# airlight.net
KiCad netlist of a schematic drawn in EAGLE
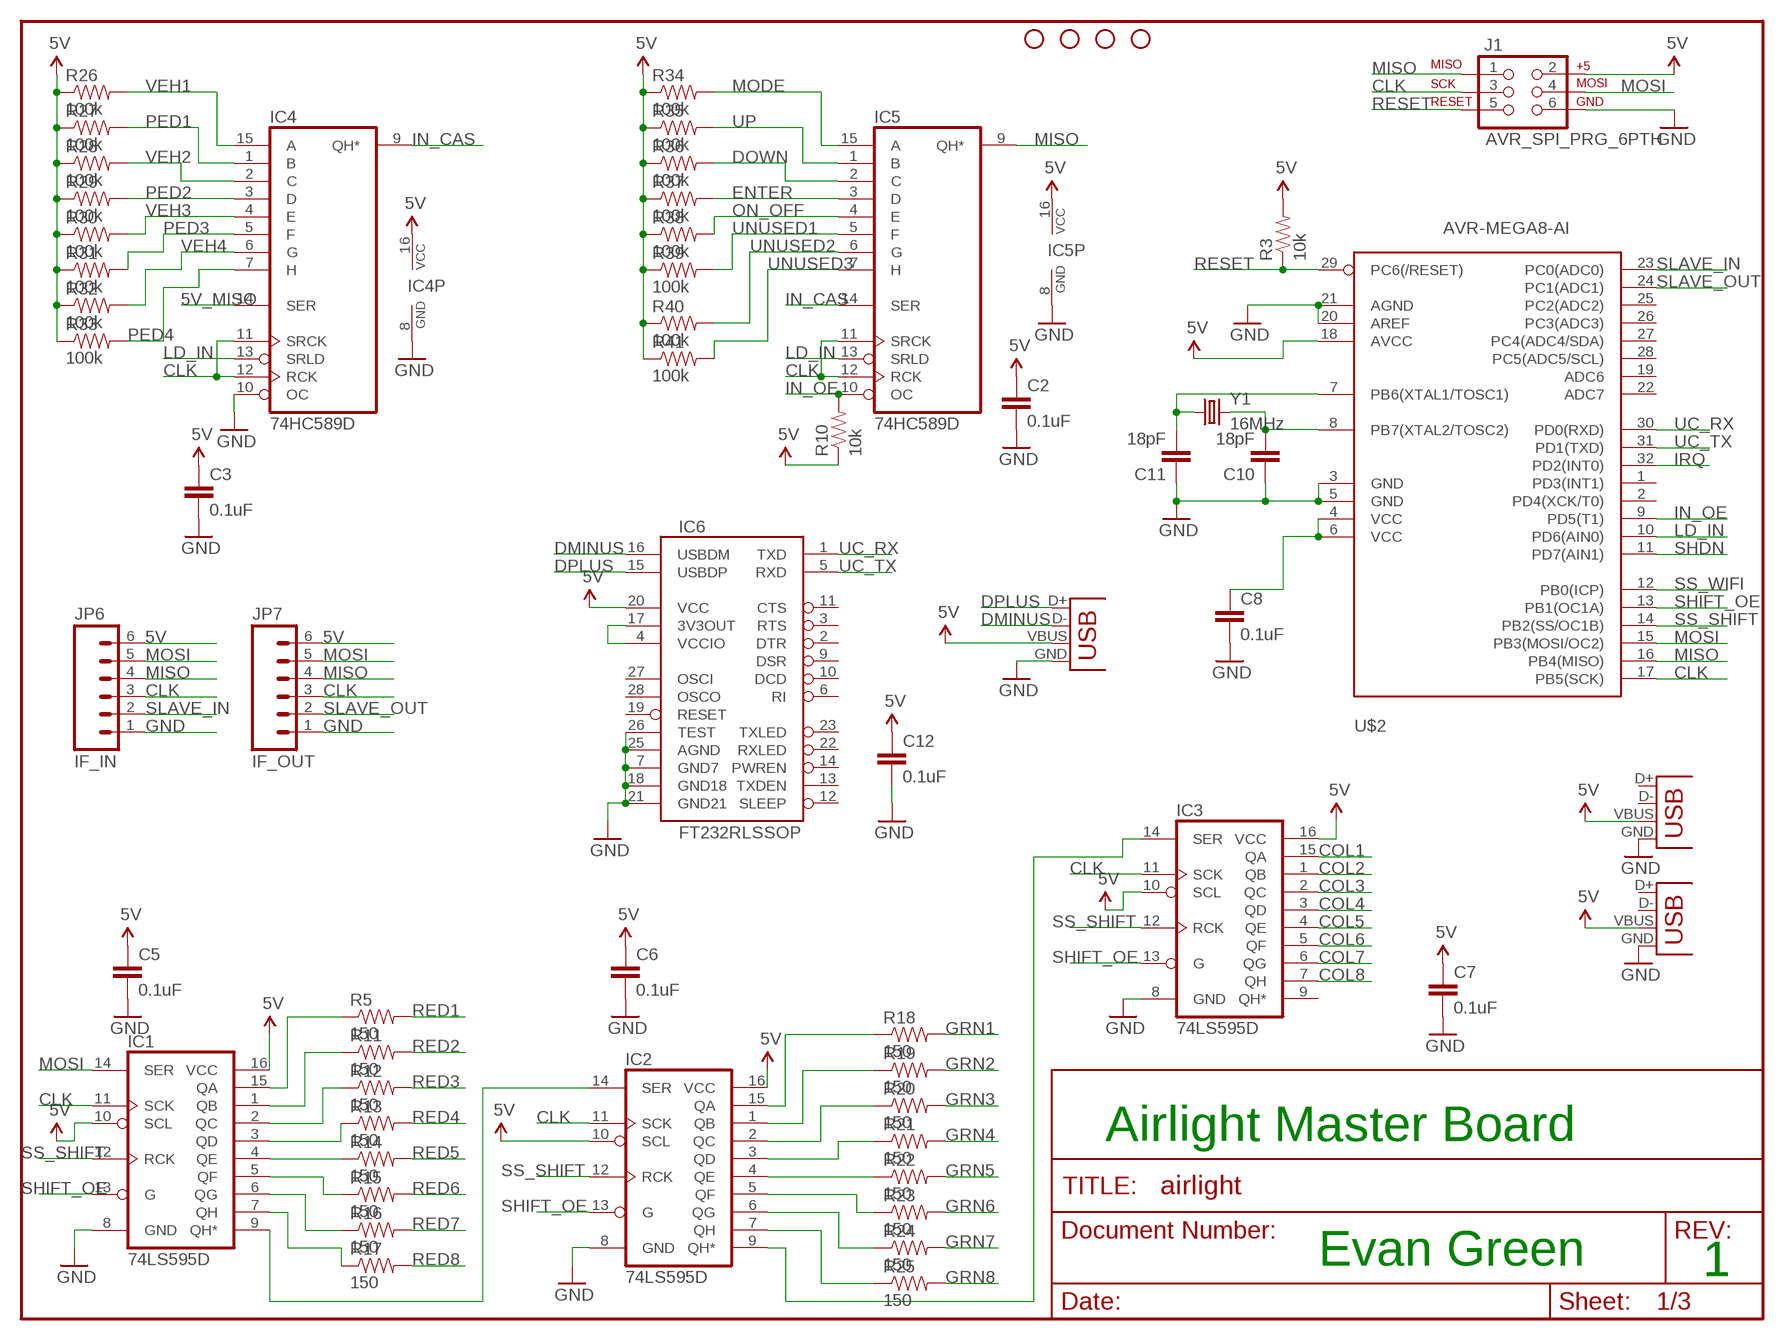
[diagram p0: schematic, sheet 1]
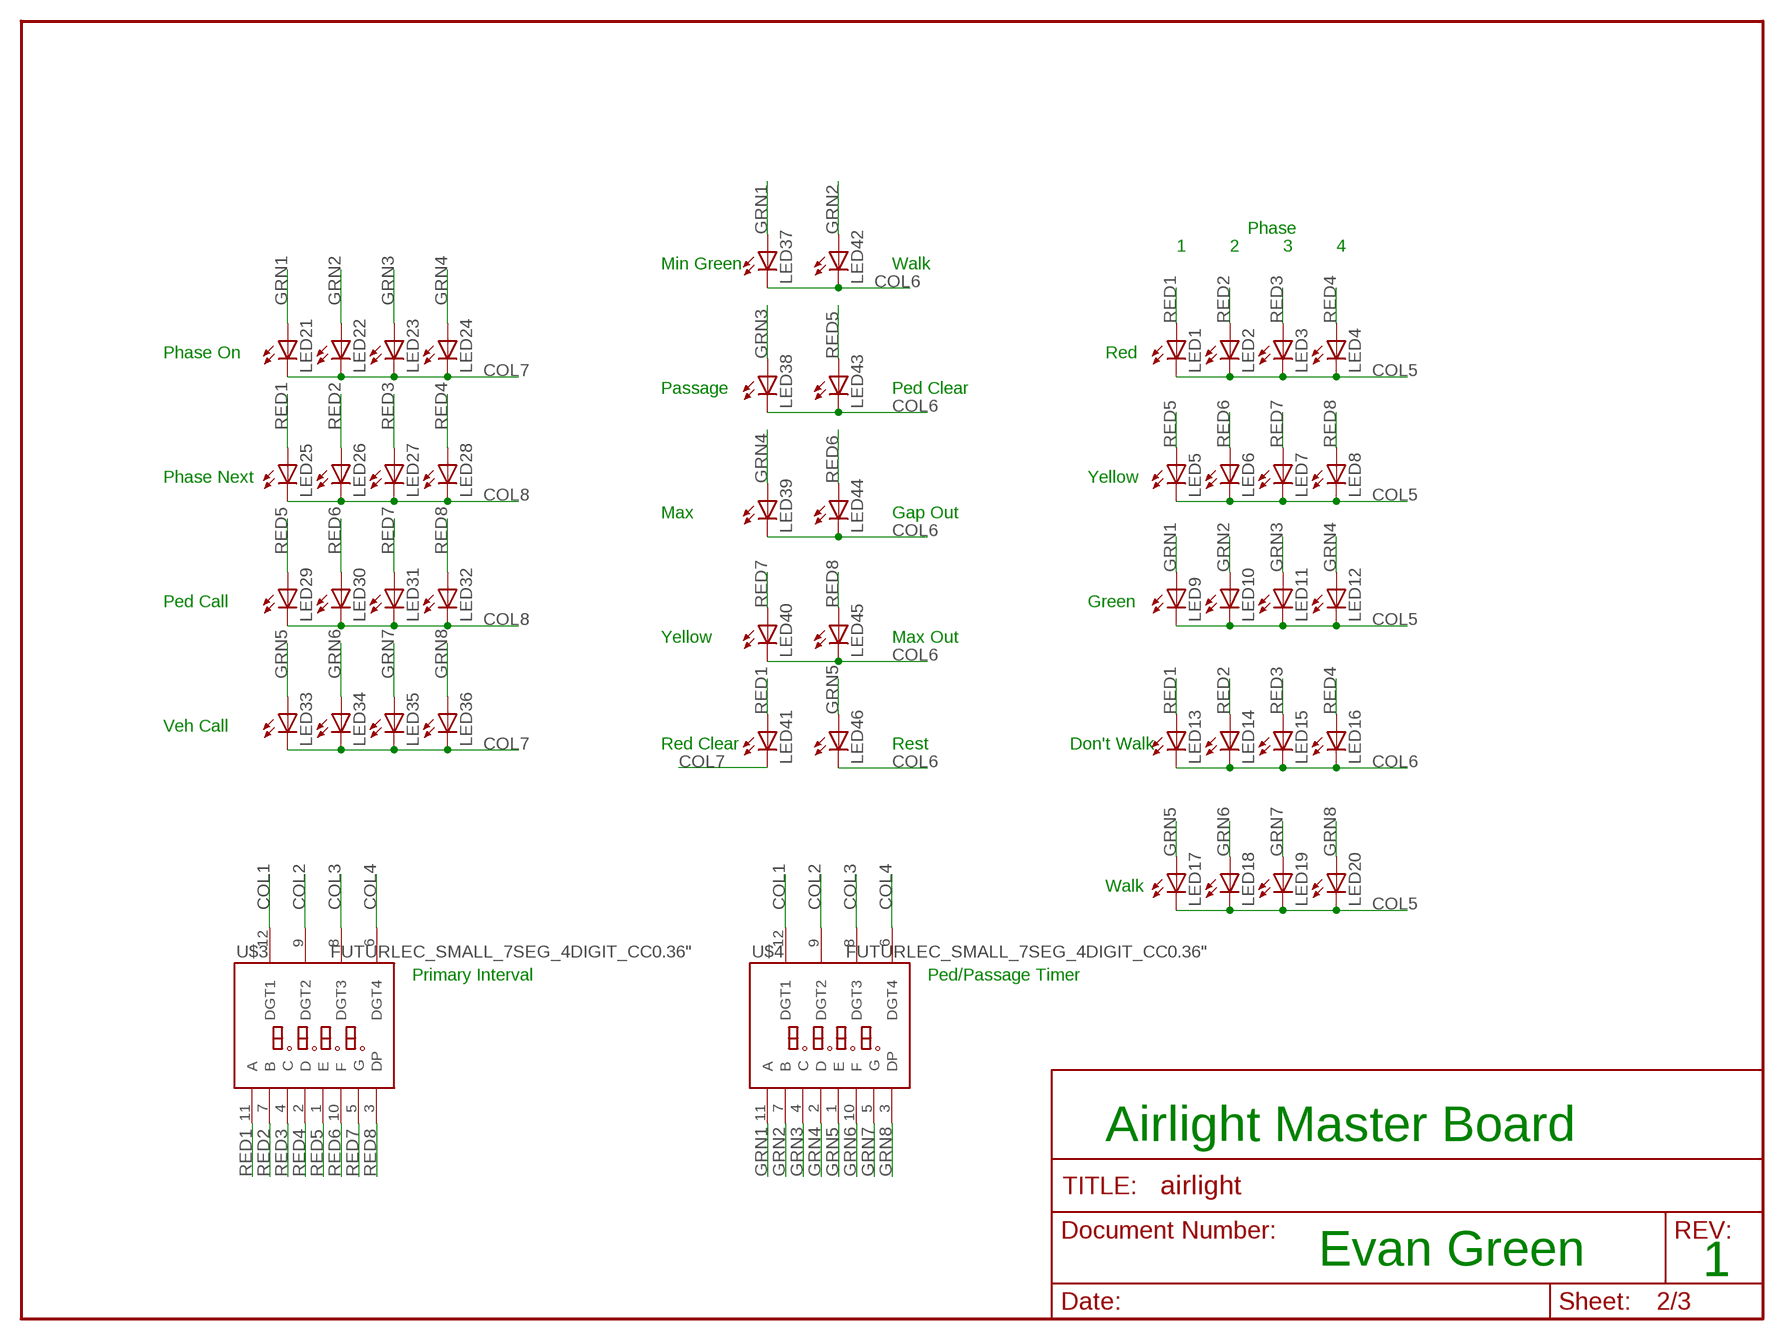
[diagram p1: schematic, sheet 2]
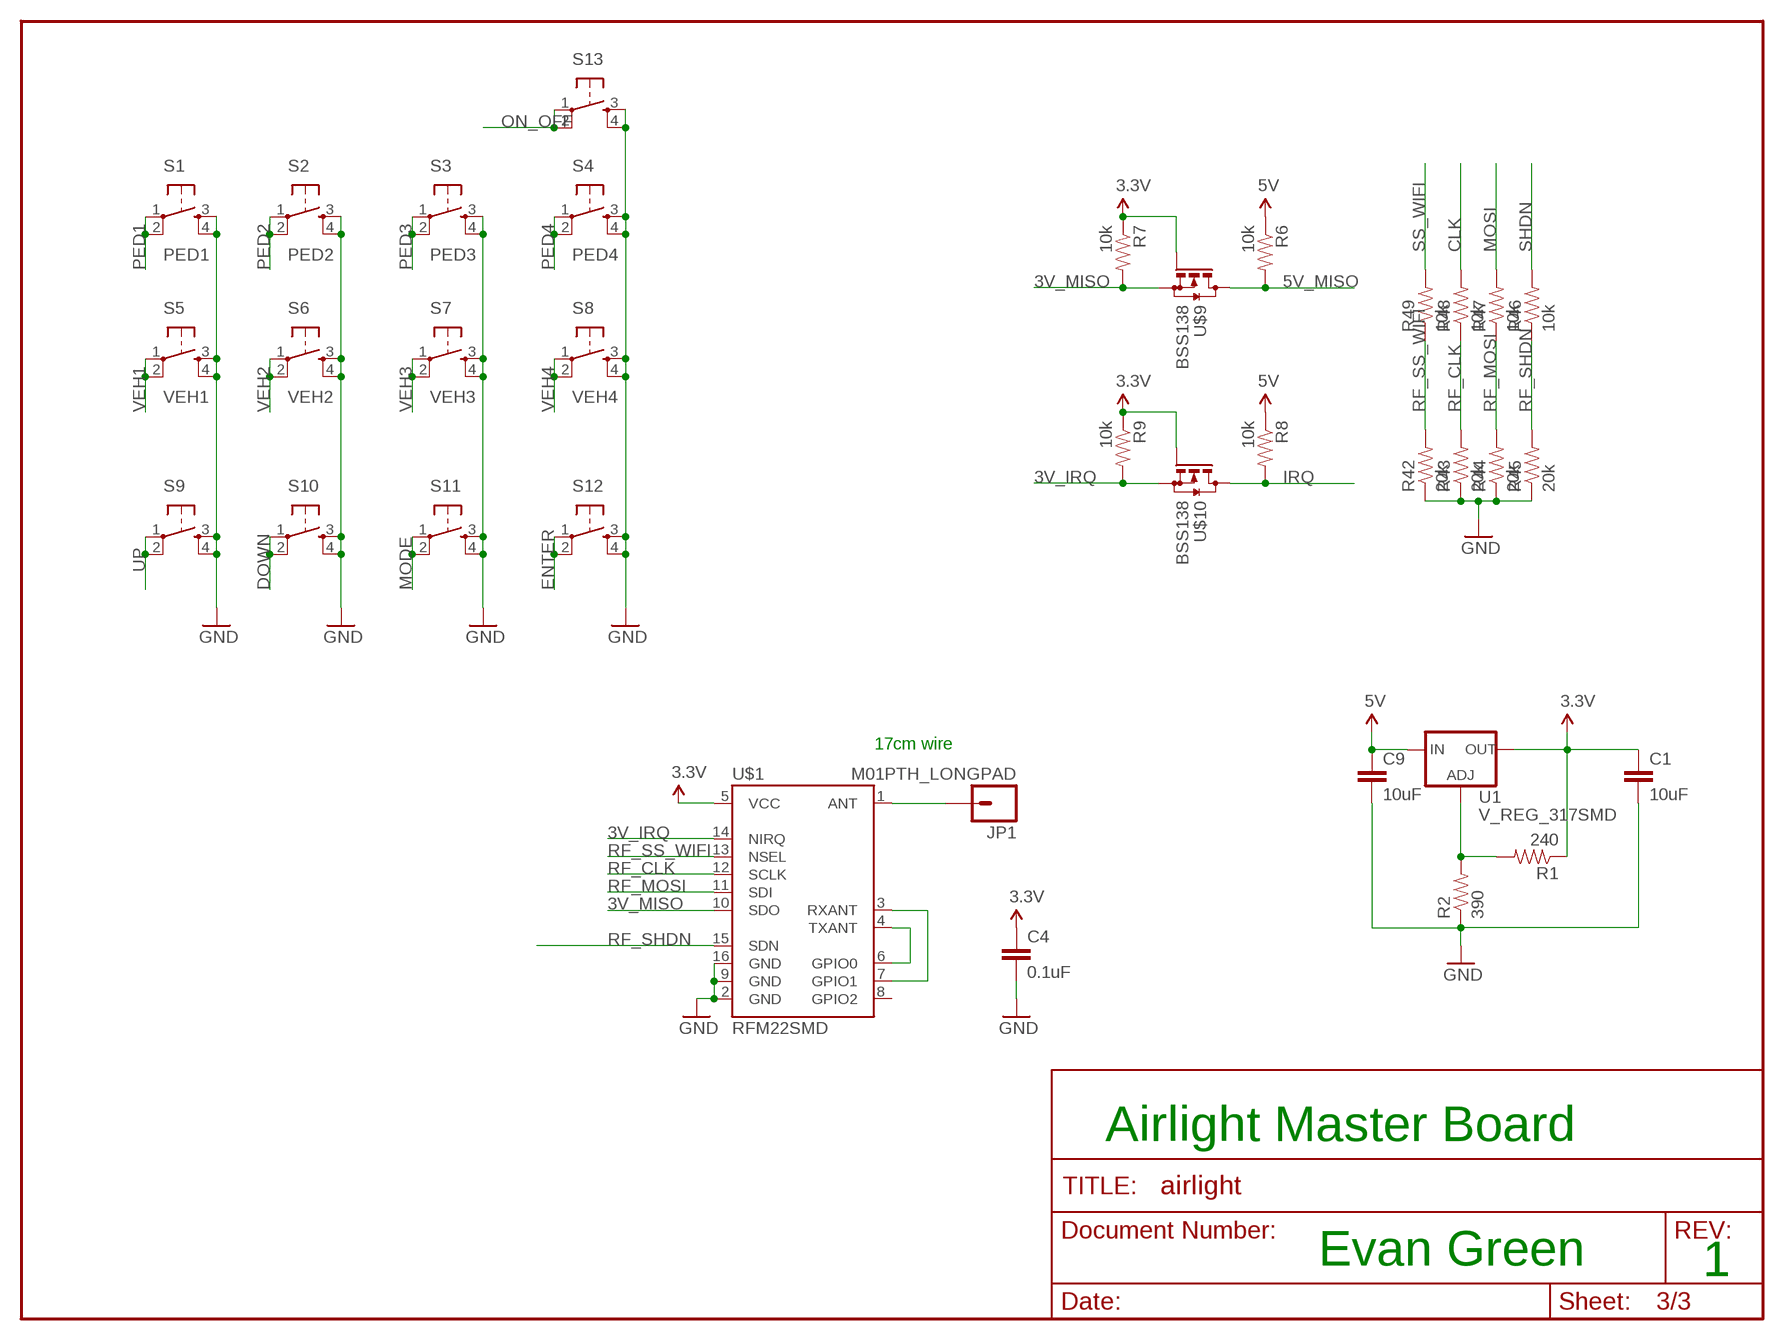
[diagram p2: schematic, sheet 3]

(export (version "E")
  (design (tool "Eeschema 10.0.6"))
  (components
    (comp (ref "LED1")
      (value "LED5MM")
      (footprint "eagle-import:LED5MM")
      (libsource (lib "eagle-import") (part "LED5MM"))
    )
    (comp (ref "LED2")
      (value "LED5MM")
      (footprint "eagle-import:LED5MM")
      (libsource (lib "eagle-import") (part "LED5MM"))
    )
    (comp (ref "LED3")
      (value "LED5MM")
      (footprint "eagle-import:LED5MM")
      (libsource (lib "eagle-import") (part "LED5MM"))
    )
    (comp (ref "LED4")
      (value "LED5MM")
      (footprint "eagle-import:LED5MM")
      (libsource (lib "eagle-import") (part "LED5MM"))
    )
    (comp (ref "LED5")
      (value "LED5MM")
      (footprint "eagle-import:LED5MM")
      (libsource (lib "eagle-import") (part "LED5MM"))
    )
    (comp (ref "LED6")
      (value "LED5MM")
      (footprint "eagle-import:LED5MM")
      (libsource (lib "eagle-import") (part "LED5MM"))
    )
    (comp (ref "LED7")
      (value "LED5MM")
      (footprint "eagle-import:LED5MM")
      (libsource (lib "eagle-import") (part "LED5MM"))
    )
    (comp (ref "LED8")
      (value "LED5MM")
      (footprint "eagle-import:LED5MM")
      (libsource (lib "eagle-import") (part "LED5MM"))
    )
    (comp (ref "LED9")
      (value "LED5MM")
      (footprint "eagle-import:LED5MM")
      (libsource (lib "eagle-import") (part "LED5MM"))
    )
    (comp (ref "LED10")
      (value "LED5MM")
      (footprint "eagle-import:LED5MM")
      (libsource (lib "eagle-import") (part "LED5MM"))
    )
    (comp (ref "LED11")
      (value "LED5MM")
      (footprint "eagle-import:LED5MM")
      (libsource (lib "eagle-import") (part "LED5MM"))
    )
    (comp (ref "LED12")
      (value "LED5MM")
      (footprint "eagle-import:LED5MM")
      (libsource (lib "eagle-import") (part "LED5MM"))
    )
    (comp (ref "LED13")
      (value "LED5MM")
      (footprint "eagle-import:LED5MM")
      (libsource (lib "eagle-import") (part "LED5MM"))
    )
    (comp (ref "LED14")
      (value "LED5MM")
      (footprint "eagle-import:LED5MM")
      (libsource (lib "eagle-import") (part "LED5MM"))
    )
    (comp (ref "LED15")
      (value "LED5MM")
      (footprint "eagle-import:LED5MM")
      (libsource (lib "eagle-import") (part "LED5MM"))
    )
    (comp (ref "LED16")
      (value "LED5MM")
      (footprint "eagle-import:LED5MM")
      (libsource (lib "eagle-import") (part "LED5MM"))
    )
    (comp (ref "LED17")
      (value "LED5MM")
      (footprint "eagle-import:LED5MM")
      (libsource (lib "eagle-import") (part "LED5MM"))
    )
    (comp (ref "LED18")
      (value "LED5MM")
      (footprint "eagle-import:LED5MM")
      (libsource (lib "eagle-import") (part "LED5MM"))
    )
    (comp (ref "LED19")
      (value "LED5MM")
      (footprint "eagle-import:LED5MM")
      (libsource (lib "eagle-import") (part "LED5MM"))
    )
    (comp (ref "LED20")
      (value "LED5MM")
      (footprint "eagle-import:LED5MM")
      (libsource (lib "eagle-import") (part "LED5MM"))
    )
    (comp (ref "LED21")
      (value "LED5MM")
      (footprint "eagle-import:LED5MM")
      (libsource (lib "eagle-import") (part "LED5MM"))
    )
    (comp (ref "LED22")
      (value "LED5MM")
      (footprint "eagle-import:LED5MM")
      (libsource (lib "eagle-import") (part "LED5MM"))
    )
    (comp (ref "LED23")
      (value "LED5MM")
      (footprint "eagle-import:LED5MM")
      (libsource (lib "eagle-import") (part "LED5MM"))
    )
    (comp (ref "LED24")
      (value "LED5MM")
      (footprint "eagle-import:LED5MM")
      (libsource (lib "eagle-import") (part "LED5MM"))
    )
    (comp (ref "LED25")
      (value "LED5MM")
      (footprint "eagle-import:LED5MM")
      (libsource (lib "eagle-import") (part "LED5MM"))
    )
    (comp (ref "LED26")
      (value "LED5MM")
      (footprint "eagle-import:LED5MM")
      (libsource (lib "eagle-import") (part "LED5MM"))
    )
    (comp (ref "LED27")
      (value "LED5MM")
      (footprint "eagle-import:LED5MM")
      (libsource (lib "eagle-import") (part "LED5MM"))
    )
    (comp (ref "LED28")
      (value "LED5MM")
      (footprint "eagle-import:LED5MM")
      (libsource (lib "eagle-import") (part "LED5MM"))
    )
    (comp (ref "LED29")
      (value "LED5MM")
      (footprint "eagle-import:LED5MM")
      (libsource (lib "eagle-import") (part "LED5MM"))
    )
    (comp (ref "LED30")
      (value "LED5MM")
      (footprint "eagle-import:LED5MM")
      (libsource (lib "eagle-import") (part "LED5MM"))
    )
    (comp (ref "LED31")
      (value "LED5MM")
      (footprint "eagle-import:LED5MM")
      (libsource (lib "eagle-import") (part "LED5MM"))
    )
    (comp (ref "LED32")
      (value "LED5MM")
      (footprint "eagle-import:LED5MM")
      (libsource (lib "eagle-import") (part "LED5MM"))
    )
    (comp (ref "LED33")
      (value "LED5MM")
      (footprint "eagle-import:LED5MM")
      (libsource (lib "eagle-import") (part "LED5MM"))
    )
    (comp (ref "LED34")
      (value "LED5MM")
      (footprint "eagle-import:LED5MM")
      (libsource (lib "eagle-import") (part "LED5MM"))
    )
    (comp (ref "LED35")
      (value "LED5MM")
      (footprint "eagle-import:LED5MM")
      (libsource (lib "eagle-import") (part "LED5MM"))
    )
    (comp (ref "LED36")
      (value "LED5MM")
      (footprint "eagle-import:LED5MM")
      (libsource (lib "eagle-import") (part "LED5MM"))
    )
    (comp (ref "LED37")
      (value "LED5MM")
      (footprint "eagle-import:LED5MM")
      (libsource (lib "eagle-import") (part "LED5MM"))
    )
    (comp (ref "LED38")
      (value "LED5MM")
      (footprint "eagle-import:LED5MM")
      (libsource (lib "eagle-import") (part "LED5MM"))
    )
    (comp (ref "LED39")
      (value "LED5MM")
      (footprint "eagle-import:LED5MM")
      (libsource (lib "eagle-import") (part "LED5MM"))
    )
    (comp (ref "LED40")
      (value "LED5MM")
      (footprint "eagle-import:LED5MM")
      (libsource (lib "eagle-import") (part "LED5MM"))
    )
    (comp (ref "LED41")
      (value "LED5MM")
      (footprint "eagle-import:LED5MM")
      (libsource (lib "eagle-import") (part "LED5MM"))
    )
    (comp (ref "LED42")
      (value "LED5MM")
      (footprint "eagle-import:LED5MM")
      (libsource (lib "eagle-import") (part "LED5MM"))
    )
    (comp (ref "LED43")
      (value "LED5MM")
      (footprint "eagle-import:LED5MM")
      (libsource (lib "eagle-import") (part "LED5MM"))
    )
    (comp (ref "LED44")
      (value "LED5MM")
      (footprint "eagle-import:LED5MM")
      (libsource (lib "eagle-import") (part "LED5MM"))
    )
    (comp (ref "LED45")
      (value "LED5MM")
      (footprint "eagle-import:LED5MM")
      (libsource (lib "eagle-import") (part "LED5MM"))
    )
    (comp (ref "LED46")
      (value "LED5MM")
      (footprint "eagle-import:LED5MM")
      (libsource (lib "eagle-import") (part "LED5MM"))
    )
    (comp (ref "U$3")
      (value "FUTURLEC_SMALL_7SEG_4DIGIT_CC0.36\"")
      (footprint "eagle-import:FUTURLEC_SMALL_7SEG_4DIGIT_CC")
      (libsource (lib "eagle-import") (part "FUTURLEC_SMALL_7SEG_4DIGIT_CC0.36{dblquote}"))
    )
    (comp (ref "U$4")
      (value "FUTURLEC_SMALL_7SEG_4DIGIT_CC0.36\"")
      (footprint "eagle-import:FUTURLEC_SMALL_7SEG_4DIGIT_CC")
      (libsource (lib "eagle-import") (part "FUTURLEC_SMALL_7SEG_4DIGIT_CC0.36{dblquote}"))
    )
    (comp (ref "C2")
      (value "0.1uF")
      (footprint "eagle-import:0402-CAP")
      (libsource (lib "eagle-import") (part "CAP0402-CAP"))
    )
    (comp (ref "C3")
      (value "0.1uF")
      (footprint "eagle-import:0402-CAP")
      (libsource (lib "eagle-import") (part "CAP0402-CAP"))
    )
    (comp (ref "C5")
      (value "0.1uF")
      (footprint "eagle-import:0402-CAP")
      (libsource (lib "eagle-import") (part "CAP0402-CAP"))
    )
    (comp (ref "C6")
      (value "0.1uF")
      (footprint "eagle-import:0402-CAP")
      (libsource (lib "eagle-import") (part "CAP0402-CAP"))
    )
    (comp (ref "C7")
      (value "0.1uF")
      (footprint "eagle-import:0402-CAP")
      (libsource (lib "eagle-import") (part "CAP0402-CAP"))
    )
    (comp (ref "C8")
      (value "0.1uF")
      (footprint "eagle-import:0402-CAP")
      (libsource (lib "eagle-import") (part "CAP0402-CAP"))
    )
    (comp (ref "C10")
      (value "18pF")
      (footprint "eagle-import:0402-CAP")
      (libsource (lib "eagle-import") (part "CAP0402-CAP"))
    )
    (comp (ref "C11")
      (value "18pF")
      (footprint "eagle-import:0402-CAP")
      (libsource (lib "eagle-import") (part "CAP0402-CAP"))
    )
    (comp (ref "C12")
      (value "0.1uF")
      (footprint "eagle-import:0402-CAP")
      (libsource (lib "eagle-import") (part "CAP0402-CAP"))
    )
    (comp (ref "IC1")
      (value "74LS595D")
      (footprint "eagle-import:SO16")
      (libsource (lib "eagle-import") (part "74595DLS"))
    )
    (comp (ref "IC2")
      (value "74LS595D")
      (footprint "eagle-import:SO16")
      (libsource (lib "eagle-import") (part "74595DLS"))
    )
    (comp (ref "IC3")
      (value "74LS595D")
      (footprint "eagle-import:SO16")
      (libsource (lib "eagle-import") (part "74595DLS"))
    )
    (comp (ref "IC4")
      (value "74HC589D")
      (footprint "eagle-import:SO16")
      (libsource (lib "eagle-import") (part "74589DHC"))
    )
    (comp (ref "IC5")
      (value "74HC589D")
      (footprint "eagle-import:SO16")
      (libsource (lib "eagle-import") (part "74589DHC"))
    )
    (comp (ref "IC6")
      (value "FT232RLSSOP")
      (footprint "eagle-import:SSOP28DB")
      (libsource (lib "eagle-import") (part "FT232RLSSOP"))
    )
    (comp (ref "J1")
      (value "AVR_SPI_PRG_6PTH")
      (footprint "eagle-import:2X3")
      (libsource (lib "eagle-import") (part "AVR_SPI_PRG_6PTH"))
    )
    (comp (ref "JP2")
      (value "STAND-OFF")
      (footprint "eagle-import:STAND-OFF")
      (libsource (lib "eagle-import") (part "STAND-OFF"))
    )
    (comp (ref "JP3")
      (value "STAND-OFF")
      (footprint "eagle-import:STAND-OFF")
      (libsource (lib "eagle-import") (part "STAND-OFF"))
    )
    (comp (ref "JP4")
      (value "STAND-OFF")
      (footprint "eagle-import:STAND-OFF")
      (libsource (lib "eagle-import") (part "STAND-OFF"))
    )
    (comp (ref "JP5")
      (value "STAND-OFF")
      (footprint "eagle-import:STAND-OFF")
      (libsource (lib "eagle-import") (part "STAND-OFF"))
    )
    (comp (ref "JP6")
      (value "IF_IN")
      (footprint "eagle-import:1X06")
      (libsource (lib "eagle-import") (part "M06SIP"))
    )
    (comp (ref "JP7")
      (value "IF_OUT")
      (footprint "eagle-import:1X06")
      (libsource (lib "eagle-import") (part "M06SIP"))
    )
    (comp (ref "R3")
      (value "10k")
      (footprint "eagle-import:0402-RES")
      (libsource (lib "eagle-import") (part "RESISTOR0402-RES"))
    )
    (comp (ref "R5")
      (value "150")
      (footprint "eagle-import:0402-RES")
      (libsource (lib "eagle-import") (part "RESISTOR0402-RES"))
    )
    (comp (ref "R10")
      (value "10k")
      (footprint "eagle-import:0402-RES")
      (libsource (lib "eagle-import") (part "RESISTOR0402-RES"))
    )
    (comp (ref "R11")
      (value "150")
      (footprint "eagle-import:0402-RES")
      (libsource (lib "eagle-import") (part "RESISTOR0402-RES"))
    )
    (comp (ref "R12")
      (value "150")
      (footprint "eagle-import:0402-RES")
      (libsource (lib "eagle-import") (part "RESISTOR0402-RES"))
    )
    (comp (ref "R13")
      (value "150")
      (footprint "eagle-import:0402-RES")
      (libsource (lib "eagle-import") (part "RESISTOR0402-RES"))
    )
    (comp (ref "R14")
      (value "150")
      (footprint "eagle-import:0402-RES")
      (libsource (lib "eagle-import") (part "RESISTOR0402-RES"))
    )
    (comp (ref "R15")
      (value "150")
      (footprint "eagle-import:0402-RES")
      (libsource (lib "eagle-import") (part "RESISTOR0402-RES"))
    )
    (comp (ref "R16")
      (value "150")
      (footprint "eagle-import:0402-RES")
      (libsource (lib "eagle-import") (part "RESISTOR0402-RES"))
    )
    (comp (ref "R17")
      (value "150")
      (footprint "eagle-import:0402-RES")
      (libsource (lib "eagle-import") (part "RESISTOR0402-RES"))
    )
    (comp (ref "R18")
      (value "150")
      (footprint "eagle-import:0402-RES")
      (libsource (lib "eagle-import") (part "RESISTOR0402-RES"))
    )
    (comp (ref "R19")
      (value "150")
      (footprint "eagle-import:0402-RES")
      (libsource (lib "eagle-import") (part "RESISTOR0402-RES"))
    )
    (comp (ref "R20")
      (value "150")
      (footprint "eagle-import:0402-RES")
      (libsource (lib "eagle-import") (part "RESISTOR0402-RES"))
    )
    (comp (ref "R21")
      (value "150")
      (footprint "eagle-import:0402-RES")
      (libsource (lib "eagle-import") (part "RESISTOR0402-RES"))
    )
    (comp (ref "R22")
      (value "150")
      (footprint "eagle-import:0402-RES")
      (libsource (lib "eagle-import") (part "RESISTOR0402-RES"))
    )
    (comp (ref "R23")
      (value "150")
      (footprint "eagle-import:0402-RES")
      (libsource (lib "eagle-import") (part "RESISTOR0402-RES"))
    )
    (comp (ref "R24")
      (value "150")
      (footprint "eagle-import:0402-RES")
      (libsource (lib "eagle-import") (part "RESISTOR0402-RES"))
    )
    (comp (ref "R25")
      (value "150")
      (footprint "eagle-import:0402-RES")
      (libsource (lib "eagle-import") (part "RESISTOR0402-RES"))
    )
    (comp (ref "R26")
      (value "100k")
      (footprint "eagle-import:0402-RES")
      (libsource (lib "eagle-import") (part "RESISTOR0402-RES"))
    )
    (comp (ref "R27")
      (value "100k")
      (footprint "eagle-import:0402-RES")
      (libsource (lib "eagle-import") (part "RESISTOR0402-RES"))
    )
    (comp (ref "R28")
      (value "100k")
      (footprint "eagle-import:0402-RES")
      (libsource (lib "eagle-import") (part "RESISTOR0402-RES"))
    )
    (comp (ref "R29")
      (value "100k")
      (footprint "eagle-import:0402-RES")
      (libsource (lib "eagle-import") (part "RESISTOR0402-RES"))
    )
    (comp (ref "R30")
      (value "100k")
      (footprint "eagle-import:0402-RES")
      (libsource (lib "eagle-import") (part "RESISTOR0402-RES"))
    )
    (comp (ref "R31")
      (value "100k")
      (footprint "eagle-import:0402-RES")
      (libsource (lib "eagle-import") (part "RESISTOR0402-RES"))
    )
    (comp (ref "R32")
      (value "100k")
      (footprint "eagle-import:0402-RES")
      (libsource (lib "eagle-import") (part "RESISTOR0402-RES"))
    )
    (comp (ref "R33")
      (value "100k")
      (footprint "eagle-import:0402-RES")
      (libsource (lib "eagle-import") (part "RESISTOR0402-RES"))
    )
    (comp (ref "R34")
      (value "100k")
      (footprint "eagle-import:0402-RES")
      (libsource (lib "eagle-import") (part "RESISTOR0402-RES"))
    )
    (comp (ref "R35")
      (value "100k")
      (footprint "eagle-import:0402-RES")
      (libsource (lib "eagle-import") (part "RESISTOR0402-RES"))
    )
    (comp (ref "R36")
      (value "100k")
      (footprint "eagle-import:0402-RES")
      (libsource (lib "eagle-import") (part "RESISTOR0402-RES"))
    )
    (comp (ref "R37")
      (value "100k")
      (footprint "eagle-import:0402-RES")
      (libsource (lib "eagle-import") (part "RESISTOR0402-RES"))
    )
    (comp (ref "R38")
      (value "100k")
      (footprint "eagle-import:0402-RES")
      (libsource (lib "eagle-import") (part "RESISTOR0402-RES"))
    )
    (comp (ref "R39")
      (value "100k")
      (footprint "eagle-import:0402-RES")
      (libsource (lib "eagle-import") (part "RESISTOR0402-RES"))
    )
    (comp (ref "R40")
      (value "100k")
      (footprint "eagle-import:0402-RES")
      (libsource (lib "eagle-import") (part "RESISTOR0402-RES"))
    )
    (comp (ref "R41")
      (value "100k")
      (footprint "eagle-import:0402-RES")
      (libsource (lib "eagle-import") (part "RESISTOR0402-RES"))
    )
    (comp (ref "U$2")
      (value "AVR-MEGA8-AI")
      (footprint "eagle-import:TQFP32-08")
      (libsource (lib "eagle-import") (part "AVR-MEGA8-AI"))
    )
    (comp (ref "X1")
      (value "USBSMD")
      (footprint "eagle-import:USB-MINIB")
      (libsource (lib "eagle-import") (part "USBSMD"))
    )
    (comp (ref "X2")
      (value "USBSMD")
      (footprint "eagle-import:USB-MINIB")
      (libsource (lib "eagle-import") (part "USBSMD"))
    )
    (comp (ref "X3")
      (value "USBSMD")
      (footprint "eagle-import:USB-MINIB")
      (libsource (lib "eagle-import") (part "USBSMD"))
    )
    (comp (ref "Y1")
      (value "16MHz")
      (footprint "eagle-import:HC49US")
      (libsource (lib "eagle-import") (part "CRYSTALHC49US"))
    )
    (comp (ref "C1")
      (value "10uF")
      (footprint "eagle-import:0805")
      (libsource (lib "eagle-import") (part "CAP0805"))
    )
    (comp (ref "C4")
      (value "0.1uF")
      (footprint "eagle-import:0402-CAP")
      (libsource (lib "eagle-import") (part "CAP0402-CAP"))
    )
    (comp (ref "C9")
      (value "10uF")
      (footprint "eagle-import:0805")
      (libsource (lib "eagle-import") (part "CAP0805"))
    )
    (comp (ref "JP1")
      (value "M01PTH_LONGPAD")
      (footprint "eagle-import:1X01_LONGPAD")
      (libsource (lib "eagle-import") (part "M01PTH_LONGPAD"))
    )
    (comp (ref "R1")
      (value "240")
      (footprint "eagle-import:0402-RES")
      (libsource (lib "eagle-import") (part "RESISTOR0402-RES"))
    )
    (comp (ref "R2")
      (value "390")
      (footprint "eagle-import:0402-RES")
      (libsource (lib "eagle-import") (part "RESISTOR0402-RES"))
    )
    (comp (ref "R6")
      (value "10k")
      (footprint "eagle-import:0402-RES")
      (libsource (lib "eagle-import") (part "RESISTOR0402-RES"))
    )
    (comp (ref "R7")
      (value "10k")
      (footprint "eagle-import:0402-RES")
      (libsource (lib "eagle-import") (part "RESISTOR0402-RES"))
    )
    (comp (ref "R8")
      (value "10k")
      (footprint "eagle-import:0402-RES")
      (libsource (lib "eagle-import") (part "RESISTOR0402-RES"))
    )
    (comp (ref "R9")
      (value "10k")
      (footprint "eagle-import:0402-RES")
      (libsource (lib "eagle-import") (part "RESISTOR0402-RES"))
    )
    (comp (ref "R42")
      (value "20k")
      (footprint "eagle-import:0402-RES")
      (libsource (lib "eagle-import") (part "RESISTOR0402-RES"))
    )
    (comp (ref "R43")
      (value "20k")
      (footprint "eagle-import:0402-RES")
      (libsource (lib "eagle-import") (part "RESISTOR0402-RES"))
    )
    (comp (ref "R44")
      (value "20k")
      (footprint "eagle-import:0402-RES")
      (libsource (lib "eagle-import") (part "RESISTOR0402-RES"))
    )
    (comp (ref "R45")
      (value "20k")
      (footprint "eagle-import:0402-RES")
      (libsource (lib "eagle-import") (part "RESISTOR0402-RES"))
    )
    (comp (ref "R46")
      (value "10k")
      (footprint "eagle-import:0402-RES")
      (libsource (lib "eagle-import") (part "RESISTOR0402-RES"))
    )
    (comp (ref "R47")
      (value "10k")
      (footprint "eagle-import:0402-RES")
      (libsource (lib "eagle-import") (part "RESISTOR0402-RES"))
    )
    (comp (ref "R48")
      (value "10k")
      (footprint "eagle-import:0402-RES")
      (libsource (lib "eagle-import") (part "RESISTOR0402-RES"))
    )
    (comp (ref "R49")
      (value "10k")
      (footprint "eagle-import:0402-RES")
      (libsource (lib "eagle-import") (part "RESISTOR0402-RES"))
    )
    (comp (ref "S1")
      (value "PED1")
      (footprint "eagle-import:TACTILE-PTH")
      (libsource (lib "eagle-import") (part "TAC_SWITCHPTH"))
    )
    (comp (ref "S2")
      (value "PED2")
      (footprint "eagle-import:TACTILE-PTH")
      (libsource (lib "eagle-import") (part "TAC_SWITCHPTH"))
    )
    (comp (ref "S3")
      (value "PED3")
      (footprint "eagle-import:TACTILE-PTH")
      (libsource (lib "eagle-import") (part "TAC_SWITCHPTH"))
    )
    (comp (ref "S4")
      (value "PED4")
      (footprint "eagle-import:TACTILE-PTH")
      (libsource (lib "eagle-import") (part "TAC_SWITCHPTH"))
    )
    (comp (ref "S5")
      (value "VEH1")
      (footprint "eagle-import:TACTILE-PTH")
      (libsource (lib "eagle-import") (part "TAC_SWITCHPTH"))
    )
    (comp (ref "S6")
      (value "VEH2")
      (footprint "eagle-import:TACTILE-PTH")
      (libsource (lib "eagle-import") (part "TAC_SWITCHPTH"))
    )
    (comp (ref "S7")
      (value "VEH3")
      (footprint "eagle-import:TACTILE-PTH")
      (libsource (lib "eagle-import") (part "TAC_SWITCHPTH"))
    )
    (comp (ref "S8")
      (value "VEH4")
      (footprint "eagle-import:TACTILE-PTH")
      (libsource (lib "eagle-import") (part "TAC_SWITCHPTH"))
    )
    (comp (ref "S9")
      (value "TAC_SWITCHPTH")
      (footprint "eagle-import:TACTILE-PTH")
      (libsource (lib "eagle-import") (part "TAC_SWITCHPTH"))
    )
    (comp (ref "S10")
      (value "TAC_SWITCHPTH")
      (footprint "eagle-import:TACTILE-PTH")
      (libsource (lib "eagle-import") (part "TAC_SWITCHPTH"))
    )
    (comp (ref "S11")
      (value "TAC_SWITCHPTH")
      (footprint "eagle-import:TACTILE-PTH")
      (libsource (lib "eagle-import") (part "TAC_SWITCHPTH"))
    )
    (comp (ref "S12")
      (value "TAC_SWITCHPTH")
      (footprint "eagle-import:TACTILE-PTH")
      (libsource (lib "eagle-import") (part "TAC_SWITCHPTH"))
    )
    (comp (ref "S13")
      (value "TAC_SWITCHPTH")
      (footprint "eagle-import:TACTILE-PTH")
      (libsource (lib "eagle-import") (part "TAC_SWITCHPTH"))
    )
    (comp (ref "U$1")
      (value "RFM22SMD")
      (footprint "eagle-import:RFM22-XXX-S2")
      (libsource (lib "eagle-import") (part "RFM22SMD"))
    )
    (comp (ref "U$9")
      (value "BSS138")
      (footprint "eagle-import:SOT-323")
      (libsource (lib "eagle-import") (part "BSS138"))
    )
    (comp (ref "U$10")
      (value "BSS138")
      (footprint "eagle-import:SOT-323")
      (libsource (lib "eagle-import") (part "BSS138"))
    )
    (comp (ref "U1")
      (value "V_REG_317SMD")
      (footprint "eagle-import:SOT223")
      (libsource (lib "eagle-import") (part "V_REG_317SMD"))
    )
  )
  (nets
    (net (code "1") (name "3.3V") (class "Default")
      (node (ref "C1") (pin "1") (pinfunction "1_1") (pintype "passive"))
      (node (ref "C4") (pin "1") (pinfunction "1_1") (pintype "passive"))
      (node (ref "R1") (pin "1") (pinfunction "1_1") (pintype "passive"))
      (node (ref "R7") (pin "1") (pinfunction "1_1") (pintype "passive"))
      (node (ref "R9") (pin "1") (pinfunction "1_1") (pintype "passive"))
      (node (ref "U$1") (pin "5") (pinfunction "VCC_5") (pintype "bidirectional"))
      (node (ref "U$10") (pin "1") (pinfunction "G_1") (pintype "passive"))
      (node (ref "U$9") (pin "1") (pinfunction "G_1") (pintype "passive"))
      (node (ref "U1") (pin "2") (pinfunction "OUT_2") (pintype "output"))
    )
    (net (code "2") (name "3V_IRQ") (class "Default")
      (node (ref "R9") (pin "2") (pinfunction "2_2") (pintype "passive"))
      (node (ref "U$1") (pin "14") (pinfunction "NIRQ_14") (pintype "output"))
      (node (ref "U$10") (pin "2") (pinfunction "S_2") (pintype "passive"))
    )
    (net (code "3") (name "3V_MISO") (class "Default")
      (node (ref "R7") (pin "2") (pinfunction "2_2") (pintype "passive"))
      (node (ref "U$1") (pin "10") (pinfunction "SDO_10") (pintype "output"))
      (node (ref "U$9") (pin "2") (pinfunction "S_2") (pintype "passive"))
    )
    (net (code "4") (name "5V") (class "Default")
      (node (ref "C12") (pin "1") (pinfunction "1_1") (pintype "passive"))
      (node (ref "C2") (pin "1") (pinfunction "1_1") (pintype "passive"))
      (node (ref "C3") (pin "1") (pinfunction "1_1") (pintype "passive"))
      (node (ref "C5") (pin "1") (pinfunction "1_1") (pintype "passive"))
      (node (ref "C6") (pin "1") (pinfunction "1_1") (pintype "passive"))
      (node (ref "C7") (pin "1") (pinfunction "1_1") (pintype "passive"))
      (node (ref "C9") (pin "1") (pinfunction "1_1") (pintype "passive"))
      (node (ref "IC1") (pin "10") (pinfunction "SCL_10") (pintype "input"))
      (node (ref "IC1") (pin "16") (pinfunction "VCC_16") (pintype "power_in"))
      (node (ref "IC2") (pin "10") (pinfunction "SCL_10") (pintype "input"))
      (node (ref "IC2") (pin "16") (pinfunction "VCC_16") (pintype "power_in"))
      (node (ref "IC3") (pin "10") (pinfunction "SCL_10") (pintype "input"))
      (node (ref "IC3") (pin "16") (pinfunction "VCC_16") (pintype "power_in"))
      (node (ref "IC4") (pin "16") (pinfunction "VCC_16") (pintype "power_in"))
      (node (ref "IC5") (pin "16") (pinfunction "VCC_16") (pintype "power_in"))
      (node (ref "IC6") (pin "20") (pinfunction "VCC_20") (pintype "power_in"))
      (node (ref "J1") (pin "2") (pinfunction "2_2") (pintype "passive"))
      (node (ref "JP6") (pin "6") (pinfunction "6_6") (pintype "passive"))
      (node (ref "JP7") (pin "6") (pinfunction "6_6") (pintype "passive"))
      (node (ref "R10") (pin "1") (pinfunction "1_1") (pintype "passive"))
      (node (ref "R26") (pin "1") (pinfunction "1_1") (pintype "passive"))
      (node (ref "R27") (pin "1") (pinfunction "1_1") (pintype "passive"))
      (node (ref "R28") (pin "1") (pinfunction "1_1") (pintype "passive"))
      (node (ref "R29") (pin "1") (pinfunction "1_1") (pintype "passive"))
      (node (ref "R3") (pin "2") (pinfunction "2_2") (pintype "passive"))
      (node (ref "R30") (pin "1") (pinfunction "1_1") (pintype "passive"))
      (node (ref "R31") (pin "1") (pinfunction "1_1") (pintype "passive"))
      (node (ref "R32") (pin "1") (pinfunction "1_1") (pintype "passive"))
      (node (ref "R33") (pin "1") (pinfunction "1_1") (pintype "passive"))
      (node (ref "R34") (pin "1") (pinfunction "1_1") (pintype "passive"))
      (node (ref "R35") (pin "1") (pinfunction "1_1") (pintype "passive"))
      (node (ref "R36") (pin "1") (pinfunction "1_1") (pintype "passive"))
      (node (ref "R37") (pin "1") (pinfunction "1_1") (pintype "passive"))
      (node (ref "R38") (pin "1") (pinfunction "1_1") (pintype "passive"))
      (node (ref "R39") (pin "1") (pinfunction "1_1") (pintype "passive"))
      (node (ref "R40") (pin "1") (pinfunction "1_1") (pintype "passive"))
      (node (ref "R41") (pin "1") (pinfunction "1_1") (pintype "passive"))
      (node (ref "R6") (pin "1") (pinfunction "1_1") (pintype "passive"))
      (node (ref "R8") (pin "1") (pinfunction "1_1") (pintype "passive"))
      (node (ref "U$2") (pin "18") (pinfunction "AVCC_18") (pintype "bidirectional"))
      (node (ref "U1") (pin "3") (pinfunction "IN_3") (pintype "input"))
      (node (ref "X1") (pin "VBUS") (pinfunction "VBUS_VBUS") (pintype "bidirectional"))
      (node (ref "X2") (pin "VBUS") (pinfunction "VBUS_VBUS") (pintype "bidirectional"))
      (node (ref "X3") (pin "VBUS") (pinfunction "VBUS_VBUS") (pintype "bidirectional"))
    )
    (net (code "5") (name "5V_MISO") (class "Default")
      (node (ref "IC4") (pin "14") (pinfunction "SER_14") (pintype "input"))
      (node (ref "R6") (pin "2") (pinfunction "2_2") (pintype "passive"))
      (node (ref "U$9") (pin "3") (pinfunction "D_3") (pintype "passive"))
    )
    (net (code "6") (name "CLK") (class "Default")
      (node (ref "IC1") (pin "11") (pinfunction "SCK_11") (pintype "input"))
      (node (ref "IC2") (pin "11") (pinfunction "SCK_11") (pintype "input"))
      (node (ref "IC3") (pin "11") (pinfunction "SCK_11") (pintype "input"))
      (node (ref "IC4") (pin "11") (pinfunction "SRCK_11") (pintype "input"))
      (node (ref "IC4") (pin "12") (pinfunction "RCK_12") (pintype "input"))
      (node (ref "IC5") (pin "11") (pinfunction "SRCK_11") (pintype "input"))
      (node (ref "IC5") (pin "12") (pinfunction "RCK_12") (pintype "input"))
      (node (ref "J1") (pin "3") (pinfunction "3_3") (pintype "passive"))
      (node (ref "JP6") (pin "3") (pinfunction "3_3") (pintype "passive"))
      (node (ref "JP7") (pin "3") (pinfunction "3_3") (pintype "passive"))
      (node (ref "R48") (pin "2") (pinfunction "2_2") (pintype "passive"))
      (node (ref "U$2") (pin "17") (pinfunction "PB5(SCK)_17") (pintype "bidirectional"))
    )
    (net (code "7") (name "COL1") (class "Default")
      (node (ref "IC3") (pin "15") (pinfunction "QA_15") (pintype "tri_state"))
      (node (ref "U$3") (pin "12") (pinfunction "DGT1_12") (pintype "bidirectional"))
      (node (ref "U$4") (pin "12") (pinfunction "DGT1_12") (pintype "bidirectional"))
    )
    (net (code "8") (name "COL2") (class "Default")
      (node (ref "IC3") (pin "1") (pinfunction "QB_1") (pintype "tri_state"))
      (node (ref "U$3") (pin "9") (pinfunction "DGT2_9") (pintype "bidirectional"))
      (node (ref "U$4") (pin "9") (pinfunction "DGT2_9") (pintype "bidirectional"))
    )
    (net (code "9") (name "COL3") (class "Default")
      (node (ref "IC3") (pin "2") (pinfunction "QC_2") (pintype "tri_state"))
      (node (ref "U$3") (pin "8") (pinfunction "DGT3_8") (pintype "bidirectional"))
      (node (ref "U$4") (pin "8") (pinfunction "DGT3_8") (pintype "bidirectional"))
    )
    (net (code "10") (name "COL4") (class "Default")
      (node (ref "IC3") (pin "3") (pinfunction "QD_3") (pintype "tri_state"))
      (node (ref "U$3") (pin "6") (pinfunction "DGT4_6") (pintype "bidirectional"))
      (node (ref "U$4") (pin "6") (pinfunction "DGT4_6") (pintype "bidirectional"))
    )
    (net (code "11") (name "COL5") (class "Default")
      (node (ref "IC3") (pin "4") (pinfunction "QE_4") (pintype "tri_state"))
      (node (ref "LED1") (pin "K") (pinfunction "C_K") (pintype "passive"))
      (node (ref "LED10") (pin "K") (pinfunction "C_K") (pintype "passive"))
      (node (ref "LED11") (pin "K") (pinfunction "C_K") (pintype "passive"))
      (node (ref "LED12") (pin "K") (pinfunction "C_K") (pintype "passive"))
      (node (ref "LED17") (pin "K") (pinfunction "C_K") (pintype "passive"))
      (node (ref "LED18") (pin "K") (pinfunction "C_K") (pintype "passive"))
      (node (ref "LED19") (pin "K") (pinfunction "C_K") (pintype "passive"))
      (node (ref "LED2") (pin "K") (pinfunction "C_K") (pintype "passive"))
      (node (ref "LED20") (pin "K") (pinfunction "C_K") (pintype "passive"))
      (node (ref "LED3") (pin "K") (pinfunction "C_K") (pintype "passive"))
      (node (ref "LED4") (pin "K") (pinfunction "C_K") (pintype "passive"))
      (node (ref "LED5") (pin "K") (pinfunction "C_K") (pintype "passive"))
      (node (ref "LED6") (pin "K") (pinfunction "C_K") (pintype "passive"))
      (node (ref "LED7") (pin "K") (pinfunction "C_K") (pintype "passive"))
      (node (ref "LED8") (pin "K") (pinfunction "C_K") (pintype "passive"))
      (node (ref "LED9") (pin "K") (pinfunction "C_K") (pintype "passive"))
    )
    (net (code "12") (name "COL6") (class "Default")
      (node (ref "IC3") (pin "5") (pinfunction "QF_5") (pintype "tri_state"))
      (node (ref "LED13") (pin "K") (pinfunction "C_K") (pintype "passive"))
      (node (ref "LED14") (pin "K") (pinfunction "C_K") (pintype "passive"))
      (node (ref "LED15") (pin "K") (pinfunction "C_K") (pintype "passive"))
      (node (ref "LED16") (pin "K") (pinfunction "C_K") (pintype "passive"))
      (node (ref "LED37") (pin "K") (pinfunction "C_K") (pintype "passive"))
      (node (ref "LED38") (pin "K") (pinfunction "C_K") (pintype "passive"))
      (node (ref "LED39") (pin "K") (pinfunction "C_K") (pintype "passive"))
      (node (ref "LED40") (pin "K") (pinfunction "C_K") (pintype "passive"))
      (node (ref "LED42") (pin "K") (pinfunction "C_K") (pintype "passive"))
      (node (ref "LED43") (pin "K") (pinfunction "C_K") (pintype "passive"))
      (node (ref "LED44") (pin "K") (pinfunction "C_K") (pintype "passive"))
      (node (ref "LED45") (pin "K") (pinfunction "C_K") (pintype "passive"))
      (node (ref "LED46") (pin "K") (pinfunction "C_K") (pintype "passive"))
    )
    (net (code "13") (name "COL7") (class "Default")
      (node (ref "IC3") (pin "6") (pinfunction "QG_6") (pintype "tri_state"))
      (node (ref "LED21") (pin "K") (pinfunction "C_K") (pintype "passive"))
      (node (ref "LED22") (pin "K") (pinfunction "C_K") (pintype "passive"))
      (node (ref "LED23") (pin "K") (pinfunction "C_K") (pintype "passive"))
      (node (ref "LED24") (pin "K") (pinfunction "C_K") (pintype "passive"))
      (node (ref "LED33") (pin "K") (pinfunction "C_K") (pintype "passive"))
      (node (ref "LED34") (pin "K") (pinfunction "C_K") (pintype "passive"))
      (node (ref "LED35") (pin "K") (pinfunction "C_K") (pintype "passive"))
      (node (ref "LED36") (pin "K") (pinfunction "C_K") (pintype "passive"))
      (node (ref "LED41") (pin "K") (pinfunction "C_K") (pintype "passive"))
    )
    (net (code "14") (name "COL8") (class "Default")
      (node (ref "IC3") (pin "7") (pinfunction "QH_7") (pintype "tri_state"))
      (node (ref "LED25") (pin "K") (pinfunction "C_K") (pintype "passive"))
      (node (ref "LED26") (pin "K") (pinfunction "C_K") (pintype "passive"))
      (node (ref "LED27") (pin "K") (pinfunction "C_K") (pintype "passive"))
      (node (ref "LED28") (pin "K") (pinfunction "C_K") (pintype "passive"))
      (node (ref "LED29") (pin "K") (pinfunction "C_K") (pintype "passive"))
      (node (ref "LED30") (pin "K") (pinfunction "C_K") (pintype "passive"))
      (node (ref "LED31") (pin "K") (pinfunction "C_K") (pintype "passive"))
      (node (ref "LED32") (pin "K") (pinfunction "C_K") (pintype "passive"))
    )
    (net (code "15") (name "DMINUS") (class "Default")
      (node (ref "IC6") (pin "16") (pinfunction "USBDM_16") (pintype "bidirectional"))
      (node (ref "X1") (pin "D-") (pinfunction "D-_D-") (pintype "bidirectional"))
    )
    (net (code "16") (name "DOWN") (class "Default")
      (node (ref "IC5") (pin "2") (pinfunction "C_2") (pintype "input"))
      (node (ref "R36") (pin "2") (pinfunction "2_2") (pintype "passive"))
      (node (ref "S10") (pin "1") (pinfunction "1_1") (pintype "passive"))
      (node (ref "S10") (pin "2") (pinfunction "2_2") (pintype "passive"))
    )
    (net (code "17") (name "DPLUS") (class "Default")
      (node (ref "IC6") (pin "15") (pinfunction "USBDP_15") (pintype "bidirectional"))
      (node (ref "X1") (pin "D+") (pinfunction "D+_D+") (pintype "bidirectional"))
    )
    (net (code "18") (name "ENTER") (class "Default")
      (node (ref "IC5") (pin "3") (pinfunction "D_3") (pintype "input"))
      (node (ref "R37") (pin "2") (pinfunction "2_2") (pintype "passive"))
      (node (ref "S12") (pin "1") (pinfunction "1_1") (pintype "passive"))
      (node (ref "S12") (pin "2") (pinfunction "2_2") (pintype "passive"))
    )
    (net (code "19") (name "GND") (class "Default")
      (node (ref "C1") (pin "2") (pinfunction "2_2") (pintype "passive"))
      (node (ref "C10") (pin "1") (pinfunction "1_1") (pintype "passive"))
      (node (ref "C11") (pin "1") (pinfunction "1_1") (pintype "passive"))
      (node (ref "C12") (pin "2") (pinfunction "2_2") (pintype "passive"))
      (node (ref "C2") (pin "2") (pinfunction "2_2") (pintype "passive"))
      (node (ref "C3") (pin "2") (pinfunction "2_2") (pintype "passive"))
      (node (ref "C4") (pin "2") (pinfunction "2_2") (pintype "passive"))
      (node (ref "C5") (pin "2") (pinfunction "2_2") (pintype "passive"))
      (node (ref "C6") (pin "2") (pinfunction "2_2") (pintype "passive"))
      (node (ref "C7") (pin "2") (pinfunction "2_2") (pintype "passive"))
      (node (ref "C8") (pin "2") (pinfunction "2_2") (pintype "passive"))
      (node (ref "C9") (pin "2") (pinfunction "2_2") (pintype "passive"))
      (node (ref "IC1") (pin "8") (pinfunction "GND_8") (pintype "power_in"))
      (node (ref "IC2") (pin "8") (pinfunction "GND_8") (pintype "power_in"))
      (node (ref "IC3") (pin "8") (pinfunction "GND_8") (pintype "power_in"))
      (node (ref "IC4") (pin "10") (pinfunction "OC_10") (pintype "input"))
      (node (ref "IC4") (pin "8") (pinfunction "GND_8") (pintype "power_in"))
      (node (ref "IC5") (pin "8") (pinfunction "GND_8") (pintype "power_in"))
      (node (ref "IC6") (pin "18") (pinfunction "GND18_18") (pintype "power_in"))
      (node (ref "IC6") (pin "21") (pinfunction "GND21_21") (pintype "power_in"))
      (node (ref "IC6") (pin "25") (pinfunction "AGND_25") (pintype "power_in"))
      (node (ref "IC6") (pin "26") (pinfunction "TEST_26") (pintype "input"))
      (node (ref "IC6") (pin "7") (pinfunction "GND7_7") (pintype "power_in"))
      (node (ref "J1") (pin "6") (pinfunction "6_6") (pintype "passive"))
      (node (ref "JP6") (pin "1") (pinfunction "1_1") (pintype "passive"))
      (node (ref "JP7") (pin "1") (pinfunction "1_1") (pintype "passive"))
      (node (ref "R2") (pin "1") (pinfunction "1_1") (pintype "passive"))
      (node (ref "R42") (pin "1") (pinfunction "1_1") (pintype "passive"))
      (node (ref "R43") (pin "1") (pinfunction "1_1") (pintype "passive"))
      (node (ref "R44") (pin "1") (pinfunction "1_1") (pintype "passive"))
      (node (ref "R45") (pin "1") (pinfunction "1_1") (pintype "passive"))
      (node (ref "S1") (pin "3") (pinfunction "3_3") (pintype "passive"))
      (node (ref "S1") (pin "4") (pinfunction "4_4") (pintype "passive"))
      (node (ref "S10") (pin "3") (pinfunction "3_3") (pintype "passive"))
      (node (ref "S10") (pin "4") (pinfunction "4_4") (pintype "passive"))
      (node (ref "S11") (pin "3") (pinfunction "3_3") (pintype "passive"))
      (node (ref "S11") (pin "4") (pinfunction "4_4") (pintype "passive"))
      (node (ref "S12") (pin "3") (pinfunction "3_3") (pintype "passive"))
      (node (ref "S12") (pin "4") (pinfunction "4_4") (pintype "passive"))
      (node (ref "S13") (pin "3") (pinfunction "3_3") (pintype "passive"))
      (node (ref "S13") (pin "4") (pinfunction "4_4") (pintype "passive"))
      (node (ref "S2") (pin "3") (pinfunction "3_3") (pintype "passive"))
      (node (ref "S2") (pin "4") (pinfunction "4_4") (pintype "passive"))
      (node (ref "S3") (pin "3") (pinfunction "3_3") (pintype "passive"))
      (node (ref "S3") (pin "4") (pinfunction "4_4") (pintype "passive"))
      (node (ref "S4") (pin "3") (pinfunction "3_3") (pintype "passive"))
      (node (ref "S4") (pin "4") (pinfunction "4_4") (pintype "passive"))
      (node (ref "S5") (pin "3") (pinfunction "3_3") (pintype "passive"))
      (node (ref "S5") (pin "4") (pinfunction "4_4") (pintype "passive"))
      (node (ref "S6") (pin "3") (pinfunction "3_3") (pintype "passive"))
      (node (ref "S6") (pin "4") (pinfunction "4_4") (pintype "passive"))
      (node (ref "S7") (pin "3") (pinfunction "3_3") (pintype "passive"))
      (node (ref "S7") (pin "4") (pinfunction "4_4") (pintype "passive"))
      (node (ref "S8") (pin "3") (pinfunction "3_3") (pintype "passive"))
      (node (ref "S8") (pin "4") (pinfunction "4_4") (pintype "passive"))
      (node (ref "S9") (pin "3") (pinfunction "3_3") (pintype "passive"))
      (node (ref "S9") (pin "4") (pinfunction "4_4") (pintype "passive"))
      (node (ref "U$1") (pin "16") (pinfunction "GND_16") (pintype "power_in"))
      (node (ref "U$1") (pin "2") (pinfunction "GND_2") (pintype "power_in"))
      (node (ref "U$1") (pin "9") (pinfunction "GND_9") (pintype "power_in"))
      (node (ref "U$2") (pin "20") (pinfunction "AREF_20") (pintype "bidirectional"))
      (node (ref "U$2") (pin "21") (pinfunction "AGND_21") (pintype "bidirectional"))
      (node (ref "U$2") (pin "3") (pinfunction "GND_3") (pintype "bidirectional"))
      (node (ref "U$2") (pin "5") (pinfunction "GND_5") (pintype "bidirectional"))
      (node (ref "X1") (pin "GND") (pinfunction "GND_GND") (pintype "bidirectional"))
      (node (ref "X2") (pin "GND") (pinfunction "GND_GND") (pintype "bidirectional"))
      (node (ref "X3") (pin "GND") (pinfunction "GND_GND") (pintype "bidirectional"))
    )
    (net (code "20") (name "GRN1") (class "Default")
      (node (ref "LED21") (pin "A") (pinfunction "A_A") (pintype "passive"))
      (node (ref "LED37") (pin "A") (pinfunction "A_A") (pintype "passive"))
      (node (ref "LED9") (pin "A") (pinfunction "A_A") (pintype "passive"))
      (node (ref "R18") (pin "2") (pinfunction "2_2") (pintype "passive"))
      (node (ref "U$4") (pin "11") (pinfunction "A_11") (pintype "bidirectional"))
    )
    (net (code "21") (name "GRN2") (class "Default")
      (node (ref "LED10") (pin "A") (pinfunction "A_A") (pintype "passive"))
      (node (ref "LED22") (pin "A") (pinfunction "A_A") (pintype "passive"))
      (node (ref "LED42") (pin "A") (pinfunction "A_A") (pintype "passive"))
      (node (ref "R19") (pin "2") (pinfunction "2_2") (pintype "passive"))
      (node (ref "U$4") (pin "7") (pinfunction "B_7") (pintype "bidirectional"))
    )
    (net (code "22") (name "GRN3") (class "Default")
      (node (ref "LED11") (pin "A") (pinfunction "A_A") (pintype "passive"))
      (node (ref "LED23") (pin "A") (pinfunction "A_A") (pintype "passive"))
      (node (ref "LED38") (pin "A") (pinfunction "A_A") (pintype "passive"))
      (node (ref "R20") (pin "2") (pinfunction "2_2") (pintype "passive"))
      (node (ref "U$4") (pin "4") (pinfunction "C_4") (pintype "bidirectional"))
    )
    (net (code "23") (name "GRN4") (class "Default")
      (node (ref "LED12") (pin "A") (pinfunction "A_A") (pintype "passive"))
      (node (ref "LED24") (pin "A") (pinfunction "A_A") (pintype "passive"))
      (node (ref "LED39") (pin "A") (pinfunction "A_A") (pintype "passive"))
      (node (ref "R21") (pin "2") (pinfunction "2_2") (pintype "passive"))
      (node (ref "U$4") (pin "2") (pinfunction "D_2") (pintype "bidirectional"))
    )
    (net (code "24") (name "GRN5") (class "Default")
      (node (ref "LED17") (pin "A") (pinfunction "A_A") (pintype "passive"))
      (node (ref "LED33") (pin "A") (pinfunction "A_A") (pintype "passive"))
      (node (ref "LED46") (pin "A") (pinfunction "A_A") (pintype "passive"))
      (node (ref "R22") (pin "2") (pinfunction "2_2") (pintype "passive"))
      (node (ref "U$4") (pin "1") (pinfunction "E_1") (pintype "bidirectional"))
    )
    (net (code "25") (name "GRN6") (class "Default")
      (node (ref "LED18") (pin "A") (pinfunction "A_A") (pintype "passive"))
      (node (ref "LED34") (pin "A") (pinfunction "A_A") (pintype "passive"))
      (node (ref "R23") (pin "2") (pinfunction "2_2") (pintype "passive"))
      (node (ref "U$4") (pin "10") (pinfunction "F_10") (pintype "bidirectional"))
    )
    (net (code "26") (name "GRN7") (class "Default")
      (node (ref "LED19") (pin "A") (pinfunction "A_A") (pintype "passive"))
      (node (ref "LED35") (pin "A") (pinfunction "A_A") (pintype "passive"))
      (node (ref "R24") (pin "2") (pinfunction "2_2") (pintype "passive"))
      (node (ref "U$4") (pin "5") (pinfunction "G_5") (pintype "bidirectional"))
    )
    (net (code "27") (name "GRN8") (class "Default")
      (node (ref "LED20") (pin "A") (pinfunction "A_A") (pintype "passive"))
      (node (ref "LED36") (pin "A") (pinfunction "A_A") (pintype "passive"))
      (node (ref "R25") (pin "2") (pinfunction "2_2") (pintype "passive"))
      (node (ref "U$4") (pin "3") (pinfunction "DP_3") (pintype "bidirectional"))
    )
    (net (code "28") (name "IN_CAS") (class "Default")
      (node (ref "IC4") (pin "9") (pinfunction "QH*_9") (pintype "tri_state"))
      (node (ref "IC5") (pin "14") (pinfunction "SER_14") (pintype "input"))
    )
    (net (code "29") (name "IN_OE") (class "Default")
      (node (ref "IC5") (pin "10") (pinfunction "OC_10") (pintype "input"))
      (node (ref "R10") (pin "2") (pinfunction "2_2") (pintype "passive"))
      (node (ref "U$2") (pin "9") (pinfunction "PD5(T1)_9") (pintype "bidirectional"))
    )
    (net (code "30") (name "IRQ") (class "Default")
      (node (ref "R8") (pin "2") (pinfunction "2_2") (pintype "passive"))
      (node (ref "U$10") (pin "3") (pinfunction "D_3") (pintype "passive"))
      (node (ref "U$2") (pin "32") (pinfunction "PD2(INT0)_32") (pintype "bidirectional"))
    )
    (net (code "31") (name "LD_IN") (class "Default")
      (node (ref "IC4") (pin "13") (pinfunction "SRLD_13") (pintype "input"))
      (node (ref "IC5") (pin "13") (pinfunction "SRLD_13") (pintype "input"))
      (node (ref "U$2") (pin "10") (pinfunction "PD6(AIN0)_10") (pintype "bidirectional"))
    )
    (net (code "32") (name "MISO") (class "Default")
      (node (ref "IC5") (pin "9") (pinfunction "QH*_9") (pintype "tri_state"))
      (node (ref "J1") (pin "1") (pinfunction "1_1") (pintype "passive"))
      (node (ref "JP6") (pin "4") (pinfunction "4_4") (pintype "passive"))
      (node (ref "JP7") (pin "4") (pinfunction "4_4") (pintype "passive"))
      (node (ref "U$2") (pin "16") (pinfunction "PB4(MISO)_16") (pintype "bidirectional"))
    )
    (net (code "33") (name "MODE") (class "Default")
      (node (ref "IC5") (pin "15") (pinfunction "A_15") (pintype "input"))
      (node (ref "R34") (pin "2") (pinfunction "2_2") (pintype "passive"))
      (node (ref "S11") (pin "1") (pinfunction "1_1") (pintype "passive"))
      (node (ref "S11") (pin "2") (pinfunction "2_2") (pintype "passive"))
    )
    (net (code "34") (name "MOSI") (class "Default")
      (node (ref "IC1") (pin "14") (pinfunction "SER_14") (pintype "input"))
      (node (ref "J1") (pin "4") (pinfunction "4_4") (pintype "passive"))
      (node (ref "JP6") (pin "5") (pinfunction "5_5") (pintype "passive"))
      (node (ref "JP7") (pin "5") (pinfunction "5_5") (pintype "passive"))
      (node (ref "R47") (pin "2") (pinfunction "2_2") (pintype "passive"))
      (node (ref "U$2") (pin "15") (pinfunction "PB3(MOSI/OC2)_15") (pintype "bidirectional"))
    )
    (net (code "35") (name "Net-(C8-Pad1)") (class "Default")
      (node (ref "C8") (pin "1") (pinfunction "1_1") (pintype "passive"))
      (node (ref "U$2") (pin "4") (pinfunction "VCC_4") (pintype "bidirectional"))
      (node (ref "U$2") (pin "6") (pinfunction "VCC_6") (pintype "bidirectional"))
    )
    (net (code "36") (name "Net-(IC1-QA)") (class "Default")
      (node (ref "IC1") (pin "15") (pinfunction "QA_15") (pintype "tri_state"))
      (node (ref "R5") (pin "1") (pinfunction "1_1") (pintype "passive"))
    )
    (net (code "37") (name "Net-(IC1-QB)") (class "Default")
      (node (ref "IC1") (pin "1") (pinfunction "QB_1") (pintype "tri_state"))
      (node (ref "R11") (pin "1") (pinfunction "1_1") (pintype "passive"))
    )
    (net (code "38") (name "Net-(IC1-QC)") (class "Default")
      (node (ref "IC1") (pin "2") (pinfunction "QC_2") (pintype "tri_state"))
      (node (ref "R12") (pin "1") (pinfunction "1_1") (pintype "passive"))
    )
    (net (code "39") (name "Net-(IC1-QD)") (class "Default")
      (node (ref "IC1") (pin "3") (pinfunction "QD_3") (pintype "tri_state"))
      (node (ref "R13") (pin "1") (pinfunction "1_1") (pintype "passive"))
    )
    (net (code "40") (name "Net-(IC1-QE)") (class "Default")
      (node (ref "IC1") (pin "4") (pinfunction "QE_4") (pintype "tri_state"))
      (node (ref "R14") (pin "1") (pinfunction "1_1") (pintype "passive"))
    )
    (net (code "41") (name "Net-(IC1-QF)") (class "Default")
      (node (ref "IC1") (pin "5") (pinfunction "QF_5") (pintype "tri_state"))
      (node (ref "R15") (pin "1") (pinfunction "1_1") (pintype "passive"))
    )
    (net (code "42") (name "Net-(IC1-QG)") (class "Default")
      (node (ref "IC1") (pin "6") (pinfunction "QG_6") (pintype "tri_state"))
      (node (ref "R16") (pin "1") (pinfunction "1_1") (pintype "passive"))
    )
    (net (code "43") (name "Net-(IC1-QH)") (class "Default")
      (node (ref "IC1") (pin "7") (pinfunction "QH_7") (pintype "tri_state"))
      (node (ref "R17") (pin "1") (pinfunction "1_1") (pintype "passive"))
    )
    (net (code "44") (name "Net-(IC1-QH*)") (class "Default")
      (node (ref "IC1") (pin "9") (pinfunction "QH*_9") (pintype "tri_state"))
      (node (ref "IC2") (pin "14") (pinfunction "SER_14") (pintype "input"))
    )
    (net (code "45") (name "Net-(IC2-QA)") (class "Default")
      (node (ref "IC2") (pin "15") (pinfunction "QA_15") (pintype "tri_state"))
      (node (ref "R18") (pin "1") (pinfunction "1_1") (pintype "passive"))
    )
    (net (code "46") (name "Net-(IC2-QB)") (class "Default")
      (node (ref "IC2") (pin "1") (pinfunction "QB_1") (pintype "tri_state"))
      (node (ref "R19") (pin "1") (pinfunction "1_1") (pintype "passive"))
    )
    (net (code "47") (name "Net-(IC2-QC)") (class "Default")
      (node (ref "IC2") (pin "2") (pinfunction "QC_2") (pintype "tri_state"))
      (node (ref "R20") (pin "1") (pinfunction "1_1") (pintype "passive"))
    )
    (net (code "48") (name "Net-(IC2-QD)") (class "Default")
      (node (ref "IC2") (pin "3") (pinfunction "QD_3") (pintype "tri_state"))
      (node (ref "R21") (pin "1") (pinfunction "1_1") (pintype "passive"))
    )
    (net (code "49") (name "Net-(IC2-QE)") (class "Default")
      (node (ref "IC2") (pin "4") (pinfunction "QE_4") (pintype "tri_state"))
      (node (ref "R22") (pin "1") (pinfunction "1_1") (pintype "passive"))
    )
    (net (code "50") (name "Net-(IC2-QF)") (class "Default")
      (node (ref "IC2") (pin "5") (pinfunction "QF_5") (pintype "tri_state"))
      (node (ref "R23") (pin "1") (pinfunction "1_1") (pintype "passive"))
    )
    (net (code "51") (name "Net-(IC2-QG)") (class "Default")
      (node (ref "IC2") (pin "6") (pinfunction "QG_6") (pintype "tri_state"))
      (node (ref "R24") (pin "1") (pinfunction "1_1") (pintype "passive"))
    )
    (net (code "52") (name "Net-(IC2-QH)") (class "Default")
      (node (ref "IC2") (pin "7") (pinfunction "QH_7") (pintype "tri_state"))
      (node (ref "R25") (pin "1") (pinfunction "1_1") (pintype "passive"))
    )
    (net (code "53") (name "Net-(IC2-QH*)") (class "Default")
      (node (ref "IC2") (pin "9") (pinfunction "QH*_9") (pintype "tri_state"))
      (node (ref "IC3") (pin "14") (pinfunction "SER_14") (pintype "input"))
    )
    (net (code "54") (name "Net-(IC6-3V3OUT)") (class "Default")
      (node (ref "IC6") (pin "17") (pinfunction "3V3OUT_17") (pintype "output"))
      (node (ref "IC6") (pin "4") (pinfunction "VCCIO_4") (pintype "power_in"))
    )
    (net (code "55") (name "Net-(U$1-ANT)") (class "Default")
      (node (ref "JP1") (pin "1") (pinfunction "1_1") (pintype "passive"))
      (node (ref "U$1") (pin "1") (pinfunction "ANT_1") (pintype "bidirectional"))
    )
    (net (code "56") (name "Net-(U$1-GPIO0)") (class "Default")
      (node (ref "U$1") (pin "4") (pinfunction "TXANT_4") (pintype "input"))
      (node (ref "U$1") (pin "6") (pinfunction "GPIO0_6") (pintype "bidirectional"))
    )
    (net (code "57") (name "Net-(U$1-GPIO1)") (class "Default")
      (node (ref "U$1") (pin "3") (pinfunction "RXANT_3") (pintype "input"))
      (node (ref "U$1") (pin "7") (pinfunction "GPIO1_7") (pintype "bidirectional"))
    )
    (net (code "58") (name "Net-(U$2-PB6(XTAL1{slash}TOSC1))") (class "Default")
      (node (ref "C11") (pin "2") (pinfunction "2_2") (pintype "passive"))
      (node (ref "U$2") (pin "7") (pinfunction "PB6(XTAL1/TOSC1)_7") (pintype "bidirectional"))
      (node (ref "Y1") (pin "1") (pinfunction "1_1") (pintype "passive"))
    )
    (net (code "59") (name "Net-(U$2-PB7(XTAL2{slash}TOSC2))") (class "Default")
      (node (ref "C10") (pin "2") (pinfunction "2_2") (pintype "passive"))
      (node (ref "U$2") (pin "8") (pinfunction "PB7(XTAL2/TOSC2)_8") (pintype "bidirectional"))
      (node (ref "Y1") (pin "2") (pinfunction "2_2") (pintype "passive"))
    )
    (net (code "60") (name "Net-(U1-ADJ)") (class "Default")
      (node (ref "R1") (pin "2") (pinfunction "2_2") (pintype "passive"))
      (node (ref "R2") (pin "2") (pinfunction "2_2") (pintype "passive"))
      (node (ref "U1") (pin "1") (pinfunction "ADJ_1") (pintype "input"))
    )
    (net (code "61") (name "ON_OFF") (class "Default")
      (node (ref "IC5") (pin "4") (pinfunction "E_4") (pintype "input"))
      (node (ref "R38") (pin "2") (pinfunction "2_2") (pintype "passive"))
      (node (ref "S13") (pin "1") (pinfunction "1_1") (pintype "passive"))
      (node (ref "S13") (pin "2") (pinfunction "2_2") (pintype "passive"))
    )
    (net (code "62") (name "PED1") (class "Default")
      (node (ref "IC4") (pin "1") (pinfunction "B_1") (pintype "input"))
      (node (ref "R27") (pin "2") (pinfunction "2_2") (pintype "passive"))
      (node (ref "S1") (pin "1") (pinfunction "1_1") (pintype "passive"))
      (node (ref "S1") (pin "2") (pinfunction "2_2") (pintype "passive"))
    )
    (net (code "63") (name "PED2") (class "Default")
      (node (ref "IC4") (pin "3") (pinfunction "D_3") (pintype "input"))
      (node (ref "R29") (pin "2") (pinfunction "2_2") (pintype "passive"))
      (node (ref "S2") (pin "1") (pinfunction "1_1") (pintype "passive"))
      (node (ref "S2") (pin "2") (pinfunction "2_2") (pintype "passive"))
    )
    (net (code "64") (name "PED3") (class "Default")
      (node (ref "IC4") (pin "5") (pinfunction "F_5") (pintype "input"))
      (node (ref "R31") (pin "2") (pinfunction "2_2") (pintype "passive"))
      (node (ref "S3") (pin "1") (pinfunction "1_1") (pintype "passive"))
      (node (ref "S3") (pin "2") (pinfunction "2_2") (pintype "passive"))
    )
    (net (code "65") (name "PED4") (class "Default")
      (node (ref "IC4") (pin "7") (pinfunction "H_7") (pintype "input"))
      (node (ref "R33") (pin "2") (pinfunction "2_2") (pintype "passive"))
      (node (ref "S4") (pin "1") (pinfunction "1_1") (pintype "passive"))
      (node (ref "S4") (pin "2") (pinfunction "2_2") (pintype "passive"))
    )
    (net (code "66") (name "RED1") (class "Default")
      (node (ref "LED1") (pin "A") (pinfunction "A_A") (pintype "passive"))
      (node (ref "LED13") (pin "A") (pinfunction "A_A") (pintype "passive"))
      (node (ref "LED25") (pin "A") (pinfunction "A_A") (pintype "passive"))
      (node (ref "LED41") (pin "A") (pinfunction "A_A") (pintype "passive"))
      (node (ref "R5") (pin "2") (pinfunction "2_2") (pintype "passive"))
      (node (ref "U$3") (pin "11") (pinfunction "A_11") (pintype "bidirectional"))
    )
    (net (code "67") (name "RED2") (class "Default")
      (node (ref "LED14") (pin "A") (pinfunction "A_A") (pintype "passive"))
      (node (ref "LED2") (pin "A") (pinfunction "A_A") (pintype "passive"))
      (node (ref "LED26") (pin "A") (pinfunction "A_A") (pintype "passive"))
      (node (ref "R11") (pin "2") (pinfunction "2_2") (pintype "passive"))
      (node (ref "U$3") (pin "7") (pinfunction "B_7") (pintype "bidirectional"))
    )
    (net (code "68") (name "RED3") (class "Default")
      (node (ref "LED15") (pin "A") (pinfunction "A_A") (pintype "passive"))
      (node (ref "LED27") (pin "A") (pinfunction "A_A") (pintype "passive"))
      (node (ref "LED3") (pin "A") (pinfunction "A_A") (pintype "passive"))
      (node (ref "R12") (pin "2") (pinfunction "2_2") (pintype "passive"))
      (node (ref "U$3") (pin "4") (pinfunction "C_4") (pintype "bidirectional"))
    )
    (net (code "69") (name "RED4") (class "Default")
      (node (ref "LED16") (pin "A") (pinfunction "A_A") (pintype "passive"))
      (node (ref "LED28") (pin "A") (pinfunction "A_A") (pintype "passive"))
      (node (ref "LED4") (pin "A") (pinfunction "A_A") (pintype "passive"))
      (node (ref "R13") (pin "2") (pinfunction "2_2") (pintype "passive"))
      (node (ref "U$3") (pin "2") (pinfunction "D_2") (pintype "bidirectional"))
    )
    (net (code "70") (name "RED5") (class "Default")
      (node (ref "LED29") (pin "A") (pinfunction "A_A") (pintype "passive"))
      (node (ref "LED43") (pin "A") (pinfunction "A_A") (pintype "passive"))
      (node (ref "LED5") (pin "A") (pinfunction "A_A") (pintype "passive"))
      (node (ref "R14") (pin "2") (pinfunction "2_2") (pintype "passive"))
      (node (ref "U$3") (pin "1") (pinfunction "E_1") (pintype "bidirectional"))
    )
    (net (code "71") (name "RED6") (class "Default")
      (node (ref "LED30") (pin "A") (pinfunction "A_A") (pintype "passive"))
      (node (ref "LED44") (pin "A") (pinfunction "A_A") (pintype "passive"))
      (node (ref "LED6") (pin "A") (pinfunction "A_A") (pintype "passive"))
      (node (ref "R15") (pin "2") (pinfunction "2_2") (pintype "passive"))
      (node (ref "U$3") (pin "10") (pinfunction "F_10") (pintype "bidirectional"))
    )
    (net (code "72") (name "RED7") (class "Default")
      (node (ref "LED31") (pin "A") (pinfunction "A_A") (pintype "passive"))
      (node (ref "LED40") (pin "A") (pinfunction "A_A") (pintype "passive"))
      (node (ref "LED7") (pin "A") (pinfunction "A_A") (pintype "passive"))
      (node (ref "R16") (pin "2") (pinfunction "2_2") (pintype "passive"))
      (node (ref "U$3") (pin "5") (pinfunction "G_5") (pintype "bidirectional"))
    )
    (net (code "73") (name "RED8") (class "Default")
      (node (ref "LED32") (pin "A") (pinfunction "A_A") (pintype "passive"))
      (node (ref "LED45") (pin "A") (pinfunction "A_A") (pintype "passive"))
      (node (ref "LED8") (pin "A") (pinfunction "A_A") (pintype "passive"))
      (node (ref "R17") (pin "2") (pinfunction "2_2") (pintype "passive"))
      (node (ref "U$3") (pin "3") (pinfunction "DP_3") (pintype "bidirectional"))
    )
    (net (code "74") (name "RESET") (class "Default")
      (node (ref "J1") (pin "5") (pinfunction "5_5") (pintype "passive"))
      (node (ref "R3") (pin "1") (pinfunction "1_1") (pintype "passive"))
      (node (ref "U$2") (pin "29") (pinfunction "PC6(/RESET)_29") (pintype "bidirectional"))
    )
    (net (code "75") (name "RF_CLK") (class "Default")
      (node (ref "R43") (pin "2") (pinfunction "2_2") (pintype "passive"))
      (node (ref "R48") (pin "1") (pinfunction "1_1") (pintype "passive"))
      (node (ref "U$1") (pin "12") (pinfunction "SCLK_12") (pintype "input"))
    )
    (net (code "76") (name "RF_MOSI") (class "Default")
      (node (ref "R44") (pin "2") (pinfunction "2_2") (pintype "passive"))
      (node (ref "R47") (pin "1") (pinfunction "1_1") (pintype "passive"))
      (node (ref "U$1") (pin "11") (pinfunction "SDI_11") (pintype "input"))
    )
    (net (code "77") (name "RF_SHDN") (class "Default")
      (node (ref "R45") (pin "2") (pinfunction "2_2") (pintype "passive"))
      (node (ref "R46") (pin "1") (pinfunction "1_1") (pintype "passive"))
      (node (ref "U$1") (pin "15") (pinfunction "SDN_15") (pintype "input"))
    )
    (net (code "78") (name "RF_SS_WIFI") (class "Default")
      (node (ref "R42") (pin "2") (pinfunction "2_2") (pintype "passive"))
      (node (ref "R49") (pin "1") (pinfunction "1_1") (pintype "passive"))
      (node (ref "U$1") (pin "13") (pinfunction "NSEL_13") (pintype "input"))
    )
    (net (code "79") (name "SHDN") (class "Default")
      (node (ref "R46") (pin "2") (pinfunction "2_2") (pintype "passive"))
      (node (ref "U$2") (pin "11") (pinfunction "PD7(AIN1)_11") (pintype "bidirectional"))
    )
    (net (code "80") (name "SHIFT_OE") (class "Default")
      (node (ref "IC1") (pin "13") (pinfunction "G_13") (pintype "input"))
      (node (ref "IC2") (pin "13") (pinfunction "G_13") (pintype "input"))
      (node (ref "IC3") (pin "13") (pinfunction "G_13") (pintype "input"))
      (node (ref "U$2") (pin "13") (pinfunction "PB1(OC1A)_13") (pintype "bidirectional"))
    )
    (net (code "81") (name "SLAVE_IN") (class "Default")
      (node (ref "JP6") (pin "2") (pinfunction "2_2") (pintype "passive"))
      (node (ref "U$2") (pin "23") (pinfunction "PC0(ADC0)_23") (pintype "bidirectional"))
    )
    (net (code "82") (name "SLAVE_OUT") (class "Default")
      (node (ref "JP7") (pin "2") (pinfunction "2_2") (pintype "passive"))
      (node (ref "U$2") (pin "24") (pinfunction "PC1(ADC1)_24") (pintype "bidirectional"))
    )
    (net (code "83") (name "SS_SHIFT") (class "Default")
      (node (ref "IC1") (pin "12") (pinfunction "RCK_12") (pintype "input"))
      (node (ref "IC2") (pin "12") (pinfunction "RCK_12") (pintype "input"))
      (node (ref "IC3") (pin "12") (pinfunction "RCK_12") (pintype "input"))
      (node (ref "U$2") (pin "14") (pinfunction "PB2(SS/OC1B)_14") (pintype "bidirectional"))
    )
    (net (code "84") (name "SS_WIFI") (class "Default")
      (node (ref "R49") (pin "2") (pinfunction "2_2") (pintype "passive"))
      (node (ref "U$2") (pin "12") (pinfunction "PB0(ICP)_12") (pintype "bidirectional"))
    )
    (net (code "85") (name "UC_RX") (class "Default")
      (node (ref "IC6") (pin "1") (pinfunction "TXD_1") (pintype "output"))
      (node (ref "U$2") (pin "30") (pinfunction "PD0(RXD)_30") (pintype "bidirectional"))
    )
    (net (code "86") (name "UC_TX") (class "Default")
      (node (ref "IC6") (pin "5") (pinfunction "RXD_5") (pintype "input"))
      (node (ref "U$2") (pin "31") (pinfunction "PD1(TXD)_31") (pintype "bidirectional"))
    )
    (net (code "87") (name "UNUSED1") (class "Default")
      (node (ref "IC5") (pin "5") (pinfunction "F_5") (pintype "input"))
      (node (ref "R39") (pin "2") (pinfunction "2_2") (pintype "passive"))
    )
    (net (code "88") (name "UNUSED2") (class "Default")
      (node (ref "IC5") (pin "6") (pinfunction "G_6") (pintype "input"))
      (node (ref "R40") (pin "2") (pinfunction "2_2") (pintype "passive"))
    )
    (net (code "89") (name "UNUSED3") (class "Default")
      (node (ref "IC5") (pin "7") (pinfunction "H_7") (pintype "input"))
      (node (ref "R41") (pin "2") (pinfunction "2_2") (pintype "passive"))
    )
    (net (code "90") (name "UP") (class "Default")
      (node (ref "IC5") (pin "1") (pinfunction "B_1") (pintype "input"))
      (node (ref "R35") (pin "2") (pinfunction "2_2") (pintype "passive"))
      (node (ref "S9") (pin "1") (pinfunction "1_1") (pintype "passive"))
      (node (ref "S9") (pin "2") (pinfunction "2_2") (pintype "passive"))
    )
    (net (code "91") (name "VEH1") (class "Default")
      (node (ref "IC4") (pin "15") (pinfunction "A_15") (pintype "input"))
      (node (ref "R26") (pin "2") (pinfunction "2_2") (pintype "passive"))
      (node (ref "S5") (pin "1") (pinfunction "1_1") (pintype "passive"))
      (node (ref "S5") (pin "2") (pinfunction "2_2") (pintype "passive"))
    )
    (net (code "92") (name "VEH2") (class "Default")
      (node (ref "IC4") (pin "2") (pinfunction "C_2") (pintype "input"))
      (node (ref "R28") (pin "2") (pinfunction "2_2") (pintype "passive"))
      (node (ref "S6") (pin "1") (pinfunction "1_1") (pintype "passive"))
      (node (ref "S6") (pin "2") (pinfunction "2_2") (pintype "passive"))
    )
    (net (code "93") (name "VEH3") (class "Default")
      (node (ref "IC4") (pin "4") (pinfunction "E_4") (pintype "input"))
      (node (ref "R30") (pin "2") (pinfunction "2_2") (pintype "passive"))
      (node (ref "S7") (pin "1") (pinfunction "1_1") (pintype "passive"))
      (node (ref "S7") (pin "2") (pinfunction "2_2") (pintype "passive"))
    )
    (net (code "94") (name "VEH4") (class "Default")
      (node (ref "IC4") (pin "6") (pinfunction "G_6") (pintype "input"))
      (node (ref "R32") (pin "2") (pinfunction "2_2") (pintype "passive"))
      (node (ref "S8") (pin "1") (pinfunction "1_1") (pintype "passive"))
      (node (ref "S8") (pin "2") (pinfunction "2_2") (pintype "passive"))
    )
    (net (code "95") (name "unconnected-(IC3-QH*-Pad9)") (class "Default")
      (node (ref "IC3") (pin "9") (pinfunction "QH*_9") (pintype "tri_state"))
    )
    (net (code "96") (name "unconnected-(IC6-CTS-Pad11)") (class "Default")
      (node (ref "IC6") (pin "11") (pinfunction "CTS_11") (pintype "input"))
    )
    (net (code "97") (name "unconnected-(IC6-DCD-Pad10)") (class "Default")
      (node (ref "IC6") (pin "10") (pinfunction "DCD_10") (pintype "input"))
    )
    (net (code "98") (name "unconnected-(IC6-DSR-Pad9)") (class "Default")
      (node (ref "IC6") (pin "9") (pinfunction "DSR_9") (pintype "input"))
    )
    (net (code "99") (name "unconnected-(IC6-DTR-Pad2)") (class "Default")
      (node (ref "IC6") (pin "2") (pinfunction "DTR_2") (pintype "output"))
    )
    (net (code "100") (name "unconnected-(IC6-OSCI-Pad27)") (class "Default")
      (node (ref "IC6") (pin "27") (pinfunction "OSCI_27") (pintype "input"))
    )
    (net (code "101") (name "unconnected-(IC6-OSCO-Pad28)") (class "Default")
      (node (ref "IC6") (pin "28") (pinfunction "OSCO_28") (pintype "output"))
    )
    (net (code "102") (name "unconnected-(IC6-PWREN-Pad14)") (class "Default")
      (node (ref "IC6") (pin "14") (pinfunction "PWREN_14") (pintype "input"))
    )
    (net (code "103") (name "unconnected-(IC6-RESET-Pad19)") (class "Default")
      (node (ref "IC6") (pin "19") (pinfunction "RESET_19") (pintype "input"))
    )
    (net (code "104") (name "unconnected-(IC6-RI-Pad6)") (class "Default")
      (node (ref "IC6") (pin "6") (pinfunction "RI_6") (pintype "input"))
    )
    (net (code "105") (name "unconnected-(IC6-RTS-Pad3)") (class "Default")
      (node (ref "IC6") (pin "3") (pinfunction "RTS_3") (pintype "output"))
    )
    (net (code "106") (name "unconnected-(IC6-RXLED-Pad22)") (class "Default")
      (node (ref "IC6") (pin "22") (pinfunction "RXLED_22") (pintype "input"))
    )
    (net (code "107") (name "unconnected-(IC6-SLEEP-Pad12)") (class "Default")
      (node (ref "IC6") (pin "12") (pinfunction "SLEEP_12") (pintype "input"))
    )
    (net (code "108") (name "unconnected-(IC6-TXDEN-Pad13)") (class "Default")
      (node (ref "IC6") (pin "13") (pinfunction "TXDEN_13") (pintype "input"))
    )
    (net (code "109") (name "unconnected-(IC6-TXLED-Pad23)") (class "Default")
      (node (ref "IC6") (pin "23") (pinfunction "TXLED_23") (pintype "input"))
    )
    (net (code "110") (name "unconnected-(U$1-GPIO2-Pad8)") (class "Default")
      (node (ref "U$1") (pin "8") (pinfunction "GPIO2_8") (pintype "bidirectional"))
    )
    (net (code "111") (name "unconnected-(U$2-ADC6-Pad19)") (class "Default")
      (node (ref "U$2") (pin "19") (pinfunction "ADC6_19") (pintype "bidirectional"))
    )
    (net (code "112") (name "unconnected-(U$2-ADC7-Pad22)") (class "Default")
      (node (ref "U$2") (pin "22") (pinfunction "ADC7_22") (pintype "bidirectional"))
    )
    (net (code "113") (name "unconnected-(U$2-PC2(ADC2)-Pad25)") (class "Default")
      (node (ref "U$2") (pin "25") (pinfunction "PC2(ADC2)_25") (pintype "bidirectional"))
    )
    (net (code "114") (name "unconnected-(U$2-PC3(ADC3)-Pad26)") (class "Default")
      (node (ref "U$2") (pin "26") (pinfunction "PC3(ADC3)_26") (pintype "bidirectional"))
    )
    (net (code "115") (name "unconnected-(U$2-PC4(ADC4{slash}SDA)-Pad27)") (class "Default")
      (node (ref "U$2") (pin "27") (pinfunction "PC4(ADC4/SDA)_27") (pintype "bidirectional"))
    )
    (net (code "116") (name "unconnected-(U$2-PC5(ADC5{slash}SCL)-Pad28)") (class "Default")
      (node (ref "U$2") (pin "28") (pinfunction "PC5(ADC5/SCL)_28") (pintype "bidirectional"))
    )
    (net (code "117") (name "unconnected-(U$2-PD3(INT1)-Pad1)") (class "Default")
      (node (ref "U$2") (pin "1") (pinfunction "PD3(INT1)_1") (pintype "bidirectional"))
    )
    (net (code "118") (name "unconnected-(U$2-PD4(XCK{slash}T0)-Pad2)") (class "Default")
      (node (ref "U$2") (pin "2") (pinfunction "PD4(XCK/T0)_2") (pintype "bidirectional"))
    )
    (net (code "119") (name "unconnected-(X2-PadD+)") (class "Default")
      (node (ref "X2") (pin "D+") (pinfunction "D+_D+") (pintype "bidirectional"))
    )
    (net (code "120") (name "unconnected-(X2-PadD-)") (class "Default")
      (node (ref "X2") (pin "D-") (pinfunction "D-_D-") (pintype "bidirectional"))
    )
    (net (code "121") (name "unconnected-(X3-PadD+)") (class "Default")
      (node (ref "X3") (pin "D+") (pinfunction "D+_D+") (pintype "bidirectional"))
    )
    (net (code "122") (name "unconnected-(X3-PadD-)") (class "Default")
      (node (ref "X3") (pin "D-") (pinfunction "D-_D-") (pintype "bidirectional"))
    )
  )
)
